# Module1.net
KiCad netlist of a schematic drawn in EAGLE
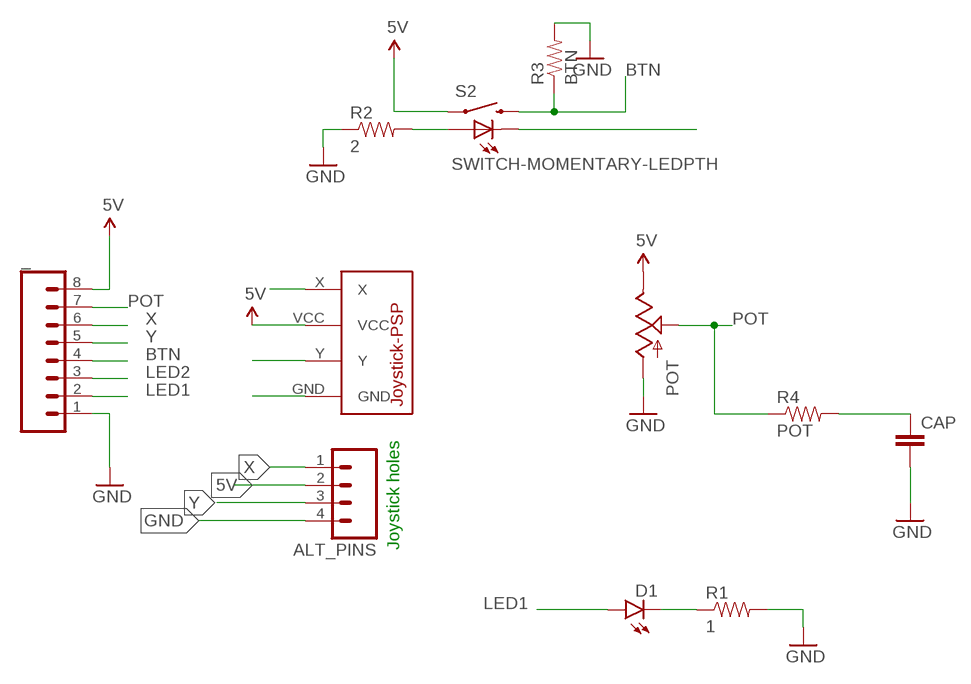
[diagram p0: schematic, sheet 1]

(export (version "E")
  (design (tool "Eeschema 10.0.6"))
  (components
    (comp (ref "ALT_PINS")
      (value "M04NO_SILK_ALL_ROUND")
      (footprint "eagle-import:1X04_NO_SILK_ALL_ROUND")
      (libsource (lib "eagle-import") (part "M04NO_SILK_ALL_ROUND"))
    )
    (comp (ref "CAP")
      (value "CAPEZ")
      (footprint "eagle-import:CAP-PTH-SMALLEZ")
      (libsource (lib "eagle-import") (part "CAPEZ"))
    )
    (comp (ref "D1")
      (value "LED3MM")
      (footprint "eagle-import:LED3MM")
      (libsource (lib "eagle-import") (part "LED3MM"))
    )
    (comp (ref "POT")
      (value "POT100K_3362U")
      (footprint "eagle-import:3362U")
      (libsource (lib "eagle-import") (part "POT100K_3362U"))
    )
    (comp (ref "R1")
      (value "1")
      (footprint "eagle-import:AXIAL-0.3-KIT")
      (libsource (lib "eagle-import") (part "10KOHM-1/6W-5%(PTH)KIT"))
    )
    (comp (ref "R2")
      (value "2")
      (footprint "eagle-import:AXIAL-0.3-KIT")
      (libsource (lib "eagle-import") (part "10KOHM-1/6W-5%(PTH)KIT"))
    )
    (comp (ref "R3")
      (value "BTN")
      (footprint "eagle-import:AXIAL-0.3-KIT")
      (libsource (lib "eagle-import") (part "10KOHM-1/6W-5%(PTH)KIT"))
    )
    (comp (ref "R4")
      (value "POT")
      (footprint "eagle-import:AXIAL-0.3-KIT")
      (libsource (lib "eagle-import") (part "10KOHM-1/6W-5%(PTH)KIT"))
    )
    (comp (ref "S2")
      (value "SWITCH-MOMENTARY-LEDPTH")
      (footprint "eagle-import:TACTILE-PTH-LED-12MM")
      (libsource (lib "eagle-import") (part "SWITCH-MOMENTARY-LEDPTH"))
    )
    (comp (ref "U$1")
      (value "JOYSTICK-PSP1000")
      (footprint "eagle-import:JOYSTICK-PSP1000")
      (libsource (lib "eagle-import") (part "JOYSTICK-PSP1000"))
    )
    (comp (ref "_")
      (value "M08")
      (footprint "eagle-import:1X08_ROUND")
      (libsource (lib "eagle-import") (part "M08"))
    )
  )
  (nets
    (net (code "1") (name "/BTN") (class "Default")
      (node (ref "R3") (pin "P$1") (pinfunction "1_P$1") (pintype "passive"))
      (node (ref "S2") (pin "2") (pinfunction "2_2") (pintype "passive"))
      (node (ref "_") (pin "4") (pinfunction "4_4") (pintype "passive"))
    )
    (net (code "2") (name "/LED1") (class "Default")
      (node (ref "D1") (pin "A") (pinfunction "A_A") (pintype "passive"))
      (node (ref "_") (pin "2") (pinfunction "2_2") (pintype "passive"))
    )
    (net (code "3") (name "/LED2") (class "Default")
      (node (ref "S2") (pin "C") (pinfunction "C_C") (pintype "passive"))
      (node (ref "_") (pin "3") (pinfunction "3_3") (pintype "passive"))
    )
    (net (code "4") (name "/POT") (class "Default")
      (node (ref "POT") (pin "P$2") (pinfunction "S_P$2") (pintype "passive"))
      (node (ref "R4") (pin "P$1") (pinfunction "1_P$1") (pintype "passive"))
      (node (ref "_") (pin "7") (pinfunction "7_7") (pintype "passive"))
    )
    (net (code "5") (name "5V") (class "Default")
      (node (ref "ALT_PINS") (pin "2") (pinfunction "2_2") (pintype "passive"))
      (node (ref "POT") (pin "P$1") (pinfunction "E_P$1") (pintype "passive"))
      (node (ref "S2") (pin "4") (pinfunction "1_4") (pintype "passive"))
      (node (ref "U$1") (pin "VCC") (pinfunction "VCC_VCC") (pintype "bidirectional"))
      (node (ref "_") (pin "8") (pinfunction "8_8") (pintype "passive"))
    )
    (net (code "6") (name "GND") (class "Default")
      (node (ref "ALT_PINS") (pin "4") (pinfunction "4_4") (pintype "passive"))
      (node (ref "CAP") (pin "2") (pinfunction "2_2") (pintype "passive"))
      (node (ref "POT") (pin "P$3") (pinfunction "A_P$3") (pintype "passive"))
      (node (ref "R1") (pin "P$2") (pinfunction "2_P$2") (pintype "passive"))
      (node (ref "R2") (pin "P$1") (pinfunction "1_P$1") (pintype "passive"))
      (node (ref "R3") (pin "P$2") (pinfunction "2_P$2") (pintype "passive"))
      (node (ref "U$1") (pin "GND") (pinfunction "GND_GND") (pintype "bidirectional"))
      (node (ref "_") (pin "1") (pinfunction "1_1") (pintype "passive"))
    )
    (net (code "7") (name "Net-(D1-C)") (class "Default")
      (node (ref "D1") (pin "K") (pinfunction "C_K") (pintype "passive"))
      (node (ref "R1") (pin "P$1") (pinfunction "1_P$1") (pintype "passive"))
    )
    (net (code "8") (name "Net-(R2-2)") (class "Default")
      (node (ref "R2") (pin "P$2") (pinfunction "2_P$2") (pintype "passive"))
      (node (ref "S2") (pin "A") (pinfunction "A_A") (pintype "passive"))
    )
    (net (code "9") (name "Net-(R4-2)") (class "Default")
      (node (ref "CAP") (pin "1") (pinfunction "1_1") (pintype "passive"))
      (node (ref "R4") (pin "P$2") (pinfunction "2_P$2") (pintype "passive"))
    )
    (net (code "10") (name "X") (class "Default")
      (node (ref "ALT_PINS") (pin "1") (pinfunction "1_1") (pintype "passive"))
      (node (ref "U$1") (pin "X") (pinfunction "X_X") (pintype "bidirectional"))
      (node (ref "_") (pin "6") (pinfunction "6_6") (pintype "passive"))
    )
    (net (code "11") (name "Y") (class "Default")
      (node (ref "ALT_PINS") (pin "3") (pinfunction "3_3") (pintype "passive"))
      (node (ref "U$1") (pin "Y") (pinfunction "Y_Y") (pintype "bidirectional"))
      (node (ref "_") (pin "5") (pinfunction "5_5") (pintype "passive"))
    )
  )
)
